# esp32-tft_gps.net
KiCad netlist of a schematic drawn in EAGLE
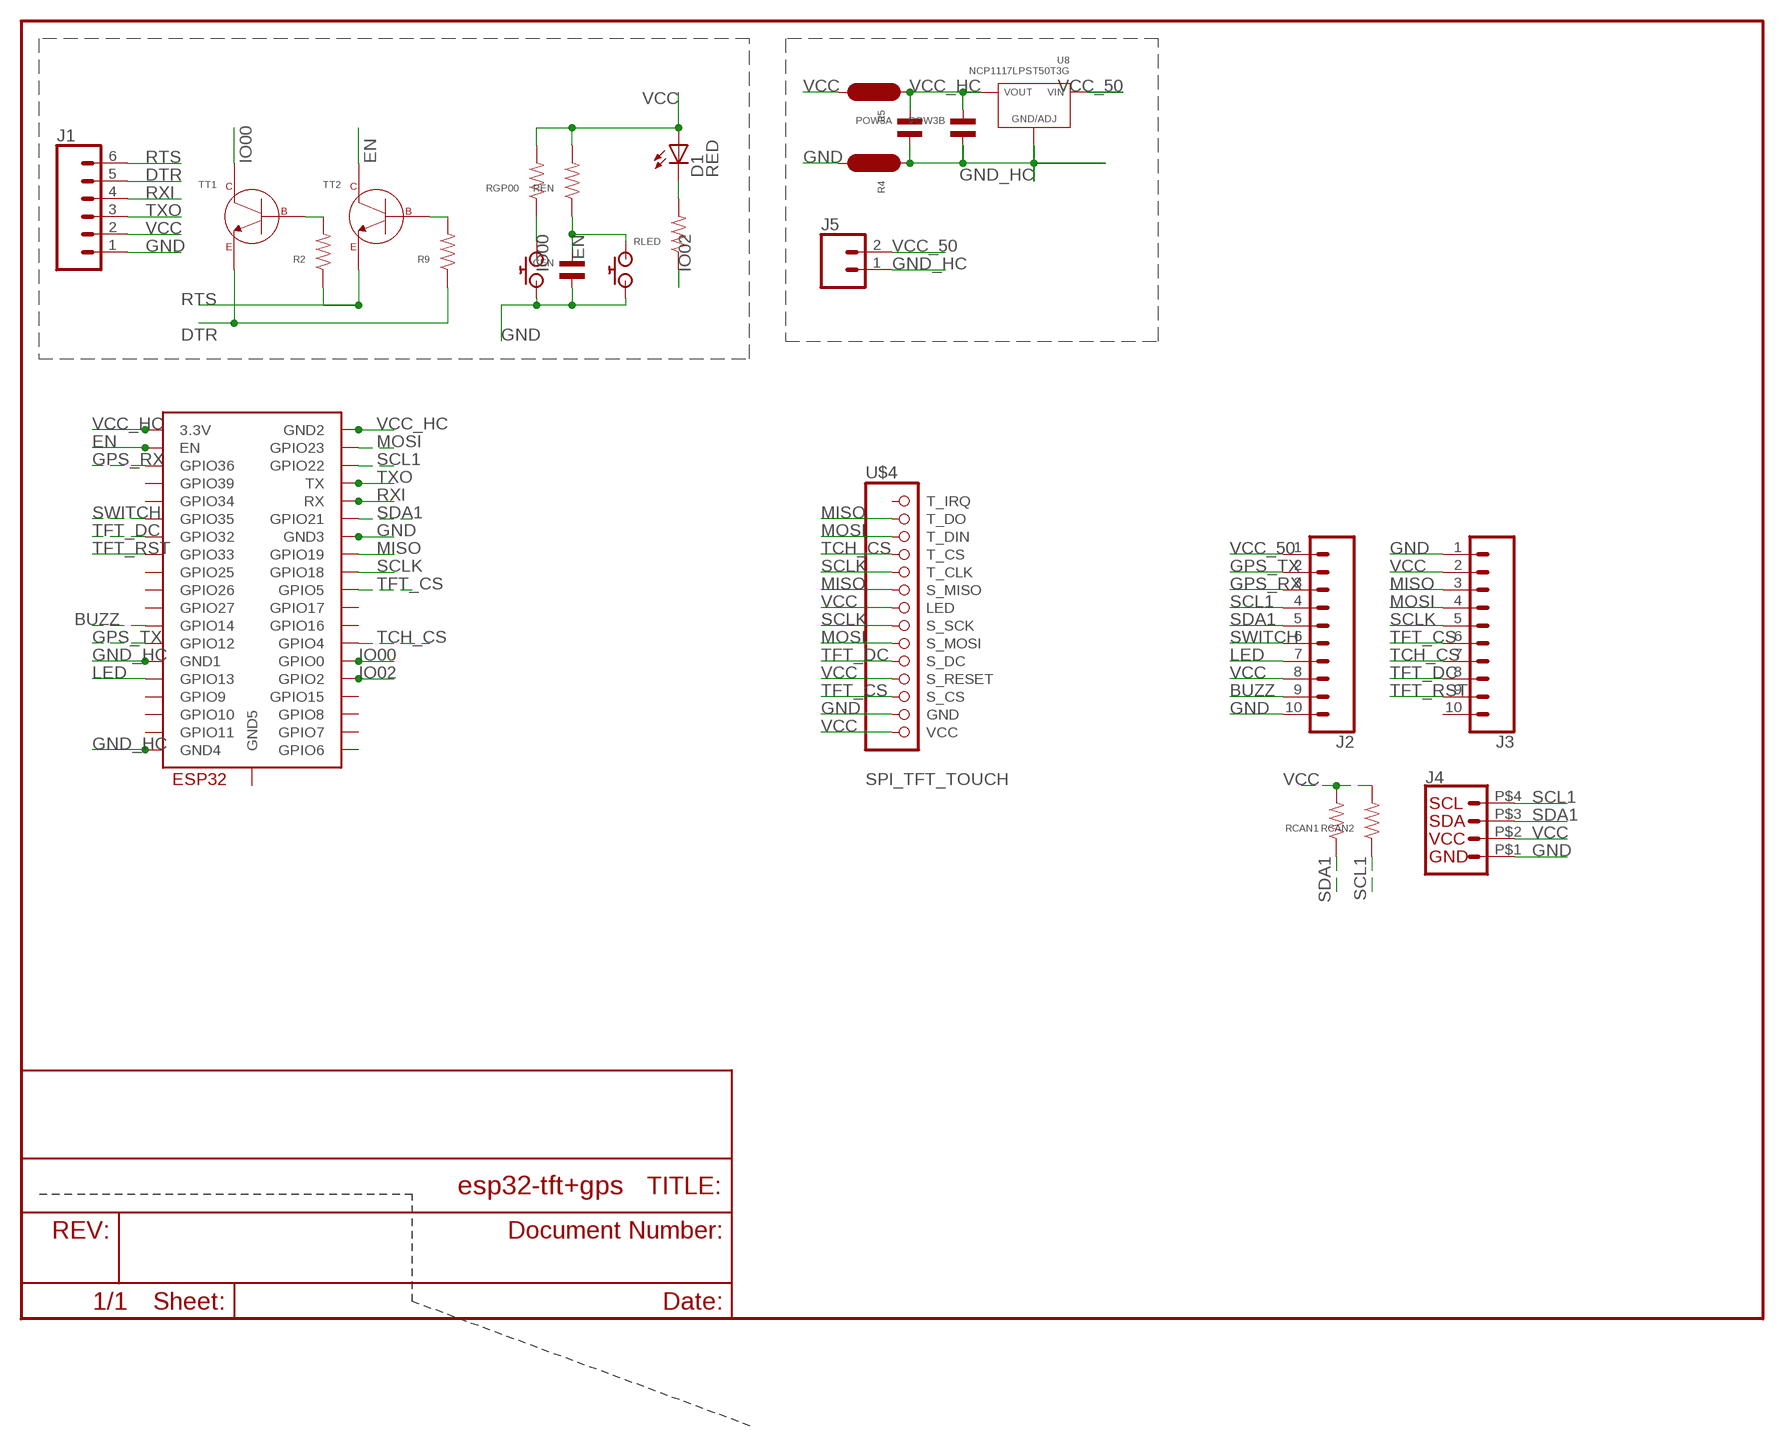
[diagram p0: schematic, sheet 1]

(export (version "E")
  (design (tool "Eeschema 10.0.6"))
  (components
    (comp (ref "CEN")
      (value "CAPACITOR_NP_0603")
      (footprint "eagle-import:C0603")
      (libsource (lib "eagle-import") (part "CAPACITOR_NP_0603"))
    )
    (comp (ref "D1")
      (value "RED")
      (footprint "eagle-import:LED-0603")
      (libsource (lib "eagle-import") (part "LED-RED0603"))
    )
    (comp (ref "J1")
      (value "CONN_06")
      (footprint "eagle-import:1X6-1.25MM-SMD")
      (libsource (lib "eagle-import") (part "CONN_06"))
    )
    (comp (ref "J2")
      (value "CONN_10")
      (footprint "eagle-import:1X10-1.25MM")
      (libsource (lib "eagle-import") (part "CONN_10"))
    )
    (comp (ref "J3")
      (value "CONN_10")
      (footprint "eagle-import:1X10-1.25MM")
      (libsource (lib "eagle-import") (part "CONN_10"))
    )
    (comp (ref "J4")
      (value "Vertical Qwiic Connector")
      (footprint "eagle-import:JST04_1MM_HOLES")
      (libsource (lib "eagle-import") (part "QWIIC_CONNECTORJST04_1MM_HOLE"))
    )
    (comp (ref "J5")
      (value "CONN_02")
      (footprint "eagle-import:1X02")
      (libsource (lib "eagle-import") (part "CONN_02"))
    )
    (comp (ref "POW3A")
      (value "CAPACITOR_NP_0603")
      (footprint "eagle-import:C0603")
      (libsource (lib "eagle-import") (part "CAPACITOR_NP_0603"))
    )
    (comp (ref "POW3B")
      (value "CAPACITOR_NP_0603")
      (footprint "eagle-import:C0603")
      (libsource (lib "eagle-import") (part "CAPACITOR_NP_0603"))
    )
    (comp (ref "R2")
      (value "RESISTOR_0603")
      (footprint "eagle-import:R0603")
      (libsource (lib "eagle-import") (part "RESISTOR_0603"))
    )
    (comp (ref "R4")
      (value "JUMPER")
      (footprint "eagle-import:R0603_JMP")
      (libsource (lib "eagle-import") (part "JUMPER"))
    )
    (comp (ref "R5")
      (value "JUMPER")
      (footprint "eagle-import:R0603_JMP")
      (libsource (lib "eagle-import") (part "JUMPER"))
    )
    (comp (ref "R9")
      (value "RESISTOR_0603")
      (footprint "eagle-import:R0603")
      (libsource (lib "eagle-import") (part "RESISTOR_0603"))
    )
    (comp (ref "RCAN1")
      (value "RESISTOR_0603")
      (footprint "eagle-import:R0603")
      (libsource (lib "eagle-import") (part "RESISTOR_0603"))
    )
    (comp (ref "RCAN2")
      (value "RESISTOR_0603")
      (footprint "eagle-import:R0603")
      (libsource (lib "eagle-import") (part "RESISTOR_0603"))
    )
    (comp (ref "REN")
      (value "RESISTOR_0603")
      (footprint "eagle-import:R0603")
      (libsource (lib "eagle-import") (part "RESISTOR_0603"))
    )
    (comp (ref "RGP00")
      (value "RESISTOR_0603")
      (footprint "eagle-import:R0603")
      (libsource (lib "eagle-import") (part "RESISTOR_0603"))
    )
    (comp (ref "RLED")
      (value "RESISTOR_0603")
      (footprint "eagle-import:R0603")
      (libsource (lib "eagle-import") (part "RESISTOR_0603"))
    )
    (comp (ref "TT1")
      (value "MF-DSC-SOT233-MMBT3904")
      (footprint "eagle-import:SOT-23-3")
      (fields (field (name "HOUSEPART") "YES"))
      (libsource (lib "eagle-import") (part "NPN_BJT_SOT-23-3MMBT3904"))
    )
    (comp (ref "TT2")
      (value "MF-DSC-SOT233-MMBT3904")
      (footprint "eagle-import:SOT-23-3")
      (fields (field (name "HOUSEPART") "YES"))
      (libsource (lib "eagle-import") (part "NPN_BJT_SOT-23-3MMBT3904"))
    )
    (comp (ref "U$1")
      (value "AMAZON_BUTTONB2010")
      (footprint "eagle-import:C2010")
      (libsource (lib "eagle-import") (part "AMAZON_BUTTONB2010"))
    )
    (comp (ref "U$2")
      (value "AMAZON_BUTTONB2010")
      (footprint "eagle-import:C2010")
      (libsource (lib "eagle-import") (part "AMAZON_BUTTONB2010"))
    )
    (comp (ref "U$3")
      (value "ESP32-WROOM")
      (footprint "eagle-import:ESP32-WROOM")
      (libsource (lib "eagle-import") (part "ESP32-WROOM"))
    )
    (comp (ref "U$4")
      (value "SPI_TFT_TOUCH")
      (footprint "eagle-import:1X14_ROUND_70")
      (libsource (lib "eagle-import") (part "SPI_TFT_TOUCH"))
    )
    (comp (ref "U8")
      (value "NCP1117LPST50T3G")
      (footprint "eagle-import:SOT-223-3")
      (fields (field (name "HOUSEPART") "NO"))
      (libsource (lib "eagle-import") (part "NCP1117LPST50T3G"))
    )
  )
  (nets
    (net (code "1") (name "/BUZZ") (class "Default")
      (node (ref "J2") (pin "9") (pinfunction "9_9") (pintype "passive"))
      (node (ref "U$3") (pin "IO14") (pinfunction "GPIO14_IO14") (pintype "bidirectional"))
    )
    (net (code "2") (name "/DTR") (class "Default")
      (node (ref "J1") (pin "5") (pinfunction "5_5") (pintype "passive"))
      (node (ref "R9") (pin "P$1") (pinfunction "P$1_P$1") (pintype "passive"))
      (node (ref "TT1") (pin "P$2") (pinfunction "EMITTER_P$2") (pintype "bidirectional"))
    )
    (net (code "3") (name "/EN") (class "Default")
      (node (ref "CEN") (pin "P$1") (pinfunction "P$1_P$1") (pintype "passive"))
      (node (ref "REN") (pin "P$1") (pinfunction "P$1_P$1") (pintype "passive"))
      (node (ref "TT2") (pin "P$3") (pinfunction "COLLECTOR_P$3") (pintype "bidirectional"))
      (node (ref "U$2") (pin "P$1") (pinfunction "P$1_P$1") (pintype "bidirectional"))
      (node (ref "U$3") (pin "EN") (pinfunction "EN_EN") (pintype "bidirectional"))
    )
    (net (code "4") (name "/GND") (class "Default")
      (node (ref "CEN") (pin "P$2") (pinfunction "P$2_P$2") (pintype "passive"))
      (node (ref "J1") (pin "1") (pinfunction "1_1") (pintype "passive"))
      (node (ref "J2") (pin "10") (pinfunction "10_10") (pintype "passive"))
      (node (ref "J3") (pin "1") (pinfunction "1_1") (pintype "passive"))
      (node (ref "J4") (pin "P$1") (pinfunction "1_P$1") (pintype "power_in"))
      (node (ref "R4") (pin "P$2") (pinfunction "P$2_P$2") (pintype "passive"))
      (node (ref "U$1") (pin "P$2") (pinfunction "P$2_P$2") (pintype "bidirectional"))
      (node (ref "U$2") (pin "P$2") (pinfunction "P$2_P$2") (pintype "bidirectional"))
      (node (ref "U$3") (pin "GND3") (pinfunction "GND3_GND3") (pintype "bidirectional"))
      (node (ref "U$4") (pin "13") (pinfunction "GND_13") (pintype "passive"))
    )
    (net (code "5") (name "/GND_HC") (class "Default")
      (node (ref "J5") (pin "1") (pinfunction "1_1") (pintype "passive"))
      (node (ref "POW3A") (pin "P$2") (pinfunction "P$2_P$2") (pintype "passive"))
      (node (ref "POW3B") (pin "P$2") (pinfunction "P$2_P$2") (pintype "passive"))
      (node (ref "R4") (pin "P$1") (pinfunction "P$1_P$1") (pintype "passive"))
      (node (ref "U$3") (pin "GND1") (pinfunction "GND1_GND1") (pintype "bidirectional"))
      (node (ref "U$3") (pin "GND4") (pinfunction "GND4_GND4") (pintype "bidirectional"))
      (node (ref "U8") (pin "P$2") (pinfunction "GND/ADJ_P$2") (pintype "bidirectional"))
    )
    (net (code "6") (name "/GPS_RX") (class "Default")
      (node (ref "J2") (pin "3") (pinfunction "3_3") (pintype "passive"))
      (node (ref "U$3") (pin "SENSOR_VP") (pinfunction "GPIO36_SENSOR_VP") (pintype "bidirectional"))
    )
    (net (code "7") (name "/GPS_TX") (class "Default")
      (node (ref "J2") (pin "2") (pinfunction "2_2") (pintype "passive"))
      (node (ref "U$3") (pin "IO12") (pinfunction "GPIO12_IO12") (pintype "bidirectional"))
    )
    (net (code "8") (name "/IO00") (class "Default")
      (node (ref "RGP00") (pin "P$1") (pinfunction "P$1_P$1") (pintype "passive"))
      (node (ref "TT1") (pin "P$3") (pinfunction "COLLECTOR_P$3") (pintype "bidirectional"))
      (node (ref "U$1") (pin "P$1") (pinfunction "P$1_P$1") (pintype "bidirectional"))
      (node (ref "U$3") (pin "IO0") (pinfunction "GPIO0_IO0") (pintype "bidirectional"))
    )
    (net (code "9") (name "/IO02") (class "Default")
      (node (ref "RLED") (pin "P$1") (pinfunction "P$1_P$1") (pintype "passive"))
      (node (ref "U$3") (pin "IO2") (pinfunction "GPIO2_IO2") (pintype "bidirectional"))
    )
    (net (code "10") (name "/LED") (class "Default")
      (node (ref "J2") (pin "7") (pinfunction "7_7") (pintype "passive"))
      (node (ref "U$3") (pin "IO13") (pinfunction "GPIO13_IO13") (pintype "bidirectional"))
    )
    (net (code "11") (name "/MISO") (class "Default")
      (node (ref "J3") (pin "3") (pinfunction "3_3") (pintype "passive"))
      (node (ref "U$3") (pin "IO19") (pinfunction "GPIO19_IO19") (pintype "bidirectional"))
      (node (ref "U$4") (pin "2") (pinfunction "T_DO_2") (pintype "passive"))
      (node (ref "U$4") (pin "6") (pinfunction "S_MISO_6") (pintype "passive"))
    )
    (net (code "12") (name "/MOSI") (class "Default")
      (node (ref "J3") (pin "4") (pinfunction "4_4") (pintype "passive"))
      (node (ref "U$3") (pin "IO23") (pinfunction "GPIO23_IO23") (pintype "bidirectional"))
      (node (ref "U$4") (pin "3") (pinfunction "T_DIN_3") (pintype "passive"))
      (node (ref "U$4") (pin "9") (pinfunction "S_MOSI_9") (pintype "passive"))
    )
    (net (code "13") (name "/RTS") (class "Default")
      (node (ref "J1") (pin "6") (pinfunction "6_6") (pintype "passive"))
      (node (ref "R2") (pin "P$1") (pinfunction "P$1_P$1") (pintype "passive"))
      (node (ref "TT2") (pin "P$2") (pinfunction "EMITTER_P$2") (pintype "bidirectional"))
    )
    (net (code "14") (name "/RXI") (class "Default")
      (node (ref "J1") (pin "4") (pinfunction "4_4") (pintype "passive"))
      (node (ref "U$3") (pin "RX") (pinfunction "RX_RX") (pintype "bidirectional"))
    )
    (net (code "15") (name "/SCL1") (class "Default")
      (node (ref "J2") (pin "4") (pinfunction "4_4") (pintype "passive"))
      (node (ref "J4") (pin "P$4") (pinfunction "4_P$4") (pintype "passive"))
      (node (ref "RCAN2") (pin "P$1") (pinfunction "P$1_P$1") (pintype "passive"))
      (node (ref "U$3") (pin "IO22") (pinfunction "GPIO22_IO22") (pintype "bidirectional"))
    )
    (net (code "16") (name "/SCLK") (class "Default")
      (node (ref "J3") (pin "5") (pinfunction "5_5") (pintype "passive"))
      (node (ref "U$3") (pin "IO18") (pinfunction "GPIO18_IO18") (pintype "bidirectional"))
      (node (ref "U$4") (pin "5") (pinfunction "T_CLK_5") (pintype "passive"))
      (node (ref "U$4") (pin "8") (pinfunction "S_SCK_8") (pintype "passive"))
    )
    (net (code "17") (name "/SDA1") (class "Default")
      (node (ref "J2") (pin "5") (pinfunction "5_5") (pintype "passive"))
      (node (ref "J4") (pin "P$3") (pinfunction "3_P$3") (pintype "passive"))
      (node (ref "RCAN1") (pin "P$1") (pinfunction "P$1_P$1") (pintype "passive"))
      (node (ref "U$3") (pin "IO21") (pinfunction "GPIO21_IO21") (pintype "bidirectional"))
    )
    (net (code "18") (name "/SWITCH") (class "Default")
      (node (ref "J2") (pin "6") (pinfunction "6_6") (pintype "passive"))
      (node (ref "U$3") (pin "IO35") (pinfunction "GPIO35_IO35") (pintype "bidirectional"))
    )
    (net (code "19") (name "/TCH_CS") (class "Default")
      (node (ref "J3") (pin "7") (pinfunction "7_7") (pintype "passive"))
      (node (ref "U$3") (pin "IO4") (pinfunction "GPIO4_IO4") (pintype "bidirectional"))
      (node (ref "U$4") (pin "4") (pinfunction "T_CS_4") (pintype "passive"))
    )
    (net (code "20") (name "/TFT_CS") (class "Default")
      (node (ref "J3") (pin "6") (pinfunction "6_6") (pintype "passive"))
      (node (ref "U$3") (pin "IO5") (pinfunction "GPIO5_IO5") (pintype "bidirectional"))
      (node (ref "U$4") (pin "12") (pinfunction "S_CS_12") (pintype "passive"))
    )
    (net (code "21") (name "/TFT_DC") (class "Default")
      (node (ref "J3") (pin "8") (pinfunction "8_8") (pintype "passive"))
      (node (ref "U$3") (pin "IO32") (pinfunction "GPIO32_IO32") (pintype "bidirectional"))
      (node (ref "U$4") (pin "10") (pinfunction "S_DC_10") (pintype "passive"))
    )
    (net (code "22") (name "/TFT_RST") (class "Default")
      (node (ref "J3") (pin "9") (pinfunction "9_9") (pintype "passive"))
      (node (ref "U$3") (pin "IO33") (pinfunction "GPIO33_IO33") (pintype "bidirectional"))
    )
    (net (code "23") (name "/TXO") (class "Default")
      (node (ref "J1") (pin "3") (pinfunction "3_3") (pintype "passive"))
      (node (ref "U$3") (pin "TX") (pinfunction "TX_TX") (pintype "bidirectional"))
    )
    (net (code "24") (name "/VCC") (class "Default")
      (node (ref "D1") (pin "A") (pinfunction "A_A") (pintype "passive"))
      (node (ref "J1") (pin "2") (pinfunction "2_2") (pintype "passive"))
      (node (ref "J2") (pin "8") (pinfunction "8_8") (pintype "passive"))
      (node (ref "J3") (pin "2") (pinfunction "2_2") (pintype "passive"))
      (node (ref "J4") (pin "P$2") (pinfunction "2_P$2") (pintype "power_in"))
      (node (ref "R5") (pin "P$2") (pinfunction "P$2_P$2") (pintype "passive"))
      (node (ref "RCAN1") (pin "P$2") (pinfunction "P$2_P$2") (pintype "passive"))
      (node (ref "RCAN2") (pin "P$2") (pinfunction "P$2_P$2") (pintype "passive"))
      (node (ref "REN") (pin "P$2") (pinfunction "P$2_P$2") (pintype "passive"))
      (node (ref "RGP00") (pin "P$2") (pinfunction "P$2_P$2") (pintype "passive"))
      (node (ref "U$4") (pin "11") (pinfunction "S_RESET_11") (pintype "passive"))
      (node (ref "U$4") (pin "14") (pinfunction "VCC_14") (pintype "passive"))
      (node (ref "U$4") (pin "7") (pinfunction "LED_7") (pintype "passive"))
    )
    (net (code "25") (name "/VCC_50") (class "Default")
      (node (ref "J2") (pin "1") (pinfunction "1_1") (pintype "passive"))
      (node (ref "J5") (pin "2") (pinfunction "2_2") (pintype "passive"))
      (node (ref "U8") (pin "P$4") (pinfunction "VIN_P$4") (pintype "bidirectional"))
    )
    (net (code "26") (name "/VCC_HC") (class "Default")
      (node (ref "POW3A") (pin "P$1") (pinfunction "P$1_P$1") (pintype "passive"))
      (node (ref "POW3B") (pin "P$1") (pinfunction "P$1_P$1") (pintype "passive"))
      (node (ref "R5") (pin "P$1") (pinfunction "P$1_P$1") (pintype "passive"))
      (node (ref "U$3") (pin "3V3") (pinfunction "3.3V_3V3") (pintype "bidirectional"))
      (node (ref "U$3") (pin "GND2") (pinfunction "GND2_GND2") (pintype "bidirectional"))
      (node (ref "U8") (pin "P$1") (pinfunction "VOUT_P$1") (pintype "bidirectional"))
      (node (ref "U8") (pin "P$3") (pinfunction "VOUT_P$3") (pintype "bidirectional"))
    )
    (net (code "27") (name "Net-(D1-PadC)") (class "Default")
      (node (ref "D1") (pin "C") (pinfunction "C_C") (pintype "passive"))
      (node (ref "RLED") (pin "P$2") (pinfunction "P$2_P$2") (pintype "passive"))
    )
    (net (code "28") (name "Net-(TT1-BASE)") (class "Default")
      (node (ref "R2") (pin "P$2") (pinfunction "P$2_P$2") (pintype "passive"))
      (node (ref "TT1") (pin "P$1") (pinfunction "BASE_P$1") (pintype "bidirectional"))
    )
    (net (code "29") (name "Net-(TT2-BASE)") (class "Default")
      (node (ref "R9") (pin "P$2") (pinfunction "P$2_P$2") (pintype "passive"))
      (node (ref "TT2") (pin "P$1") (pinfunction "BASE_P$1") (pintype "bidirectional"))
    )
    (net (code "30") (name "unconnected-(J3-Pad10)") (class "Default")
      (node (ref "J3") (pin "10") (pinfunction "10_10") (pintype "passive"))
    )
    (net (code "31") (name "unconnected-(U$3-GPIO6-PadCLK)") (class "Default")
      (node (ref "U$3") (pin "CLK") (pinfunction "GPIO6_CLK") (pintype "bidirectional"))
    )
    (net (code "32") (name "unconnected-(U$3-GPIO7-PadSD0)") (class "Default")
      (node (ref "U$3") (pin "SD0") (pinfunction "GPIO7_SD0") (pintype "bidirectional"))
    )
    (net (code "33") (name "unconnected-(U$3-GPIO8-PadSD1)") (class "Default")
      (node (ref "U$3") (pin "SD1") (pinfunction "GPIO8_SD1") (pintype "bidirectional"))
    )
    (net (code "34") (name "unconnected-(U$3-GPIO9-PadSD2)") (class "Default")
      (node (ref "U$3") (pin "SD2") (pinfunction "GPIO9_SD2") (pintype "bidirectional"))
    )
    (net (code "35") (name "unconnected-(U$3-GPIO10-PadSD3)") (class "Default")
      (node (ref "U$3") (pin "SD3") (pinfunction "GPIO10_SD3") (pintype "bidirectional"))
    )
    (net (code "36") (name "unconnected-(U$3-GPIO11-PadCMD)") (class "Default")
      (node (ref "U$3") (pin "CMD") (pinfunction "GPIO11_CMD") (pintype "bidirectional"))
    )
    (net (code "37") (name "unconnected-(U$3-GPIO15-PadIO15)") (class "Default")
      (node (ref "U$3") (pin "IO15") (pinfunction "GPIO15_IO15") (pintype "bidirectional"))
    )
    (net (code "38") (name "unconnected-(U$3-GPIO16-PadIO16)") (class "Default")
      (node (ref "U$3") (pin "IO16") (pinfunction "GPIO16_IO16") (pintype "bidirectional"))
    )
    (net (code "39") (name "unconnected-(U$3-GPIO17-PadIO17)") (class "Default")
      (node (ref "U$3") (pin "IO17") (pinfunction "GPIO17_IO17") (pintype "bidirectional"))
    )
    (net (code "40") (name "unconnected-(U$3-GPIO25-PadIO25)") (class "Default")
      (node (ref "U$3") (pin "IO25") (pinfunction "GPIO25_IO25") (pintype "bidirectional"))
    )
    (net (code "41") (name "unconnected-(U$3-GPIO26-PadIO26)") (class "Default")
      (node (ref "U$3") (pin "IO26") (pinfunction "GPIO26_IO26") (pintype "bidirectional"))
    )
    (net (code "42") (name "unconnected-(U$3-GPIO27-PadIO27)") (class "Default")
      (node (ref "U$3") (pin "IO27") (pinfunction "GPIO27_IO27") (pintype "bidirectional"))
    )
    (net (code "43") (name "unconnected-(U$3-GPIO34-PadIO34)") (class "Default")
      (node (ref "U$3") (pin "IO34") (pinfunction "GPIO34_IO34") (pintype "bidirectional"))
    )
    (net (code "44") (name "unconnected-(U$3-GPIO39-PadSENSOR_VN)") (class "Default")
      (node (ref "U$3") (pin "SENSOR_VN") (pinfunction "GPIO39_SENSOR_VN") (pintype "bidirectional"))
    )
    (net (code "45") (name "unconnected-(U$3-PadGND5)") (class "Default")
      (node (ref "U$3") (pin "GND5") (pinfunction "GND5_GND5") (pintype "bidirectional"))
    )
    (net (code "46") (name "unconnected-(U$4-T_IRQ-Pad1)") (class "Default")
      (node (ref "U$4") (pin "1") (pinfunction "T_IRQ_1") (pintype "passive"))
    )
  )
)
